# USBPort-Slave.net
KiCad netlist of a schematic drawn in Altium Designer
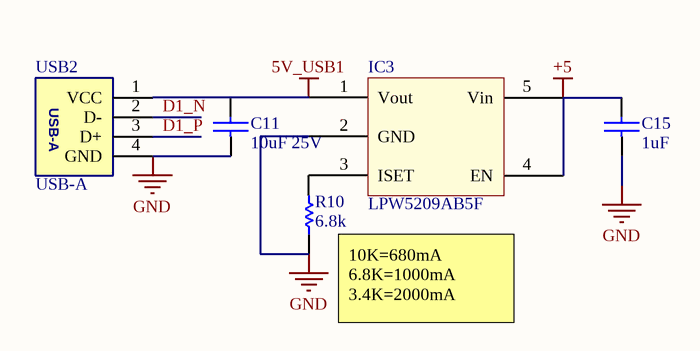
[diagram p0: USBPort-Slave.SchDoc]

(export (version "E")
  (design (tool "Eeschema 10.0.6"))
  (components
    (comp (ref "C11")
      (value "10uF 25V")
      (footprint "Capacitance:0805C")
      (description "无极性电容")
      (libsource (lib "电容") (part "CAP"))
    )
    (comp (ref "C15") (value "1uF") (footprint "0402C") (libsource (lib "电容") (part "CAP-NP")))
    (comp (ref "IC3")
      (value "LPW5209AB5F")
      (footprint "SOT23-5")
      (description "USB 限流开关")
      (libsource (lib "电源芯片") (part "LPW5209AB5F"))
    )
    (comp (ref "R10") (value "6.8k") (footprint "0402R") (libsource (lib "电阻") (part "RES")))
    (comp (ref "USB2") (value "USB-A") (footprint "USB-A/S_F") (libsource (lib "USB") (part "USB-A")))
  )
  (nets
    (net (code "1") (name "+5") (class "Default")
      (node (ref "C15") (pin "2") (pinfunction "2_2") (pintype "passive"))
      (node (ref "IC3") (pin "4") (pinfunction "EN_4") (pintype "power_in"))
      (node (ref "IC3") (pin "5") (pinfunction "Vin_5") (pintype "power_in"))
    )
    (net (code "2") (name "/D1_N") (class "Default")
      (node (ref "USB2") (pin "2") (pinfunction "D-_2") (pintype "passive"))
    )
    (net (code "3") (name "/D1_P") (class "Default")
      (node (ref "USB2") (pin "3") (pinfunction "D+_3") (pintype "passive"))
    )
    (net (code "4") (name "5V_USB1") (class "Default")
      (node (ref "C11") (pin "2") (pinfunction "2_2") (pintype "passive"))
      (node (ref "IC3") (pin "1") (pinfunction "Vout_1") (pintype "power_in"))
      (node (ref "USB2") (pin "1") (pinfunction "VCC_1") (pintype "passive"))
    )
    (net (code "5") (name "GND") (class "Default")
      (node (ref "C11") (pin "1") (pinfunction "1_1") (pintype "passive"))
      (node (ref "C15") (pin "1") (pinfunction "1_1") (pintype "passive"))
      (node (ref "IC3") (pin "2") (pinfunction "GND_2") (pintype "power_in"))
      (node (ref "R10") (pin "1") (pinfunction "1_1") (pintype "passive"))
      (node (ref "USB2") (pin "4") (pinfunction "GND_4") (pintype "passive"))
    )
    (net (code "6") (name "Net-(IC3-ISET)") (class "Default")
      (node (ref "IC3") (pin "3") (pinfunction "ISET_3") (pintype "power_in"))
      (node (ref "R10") (pin "2") (pinfunction "2_2") (pintype "passive"))
    )
  )
)
